# Driver.net
KiCad netlist of a schematic drawn in Altium Designer
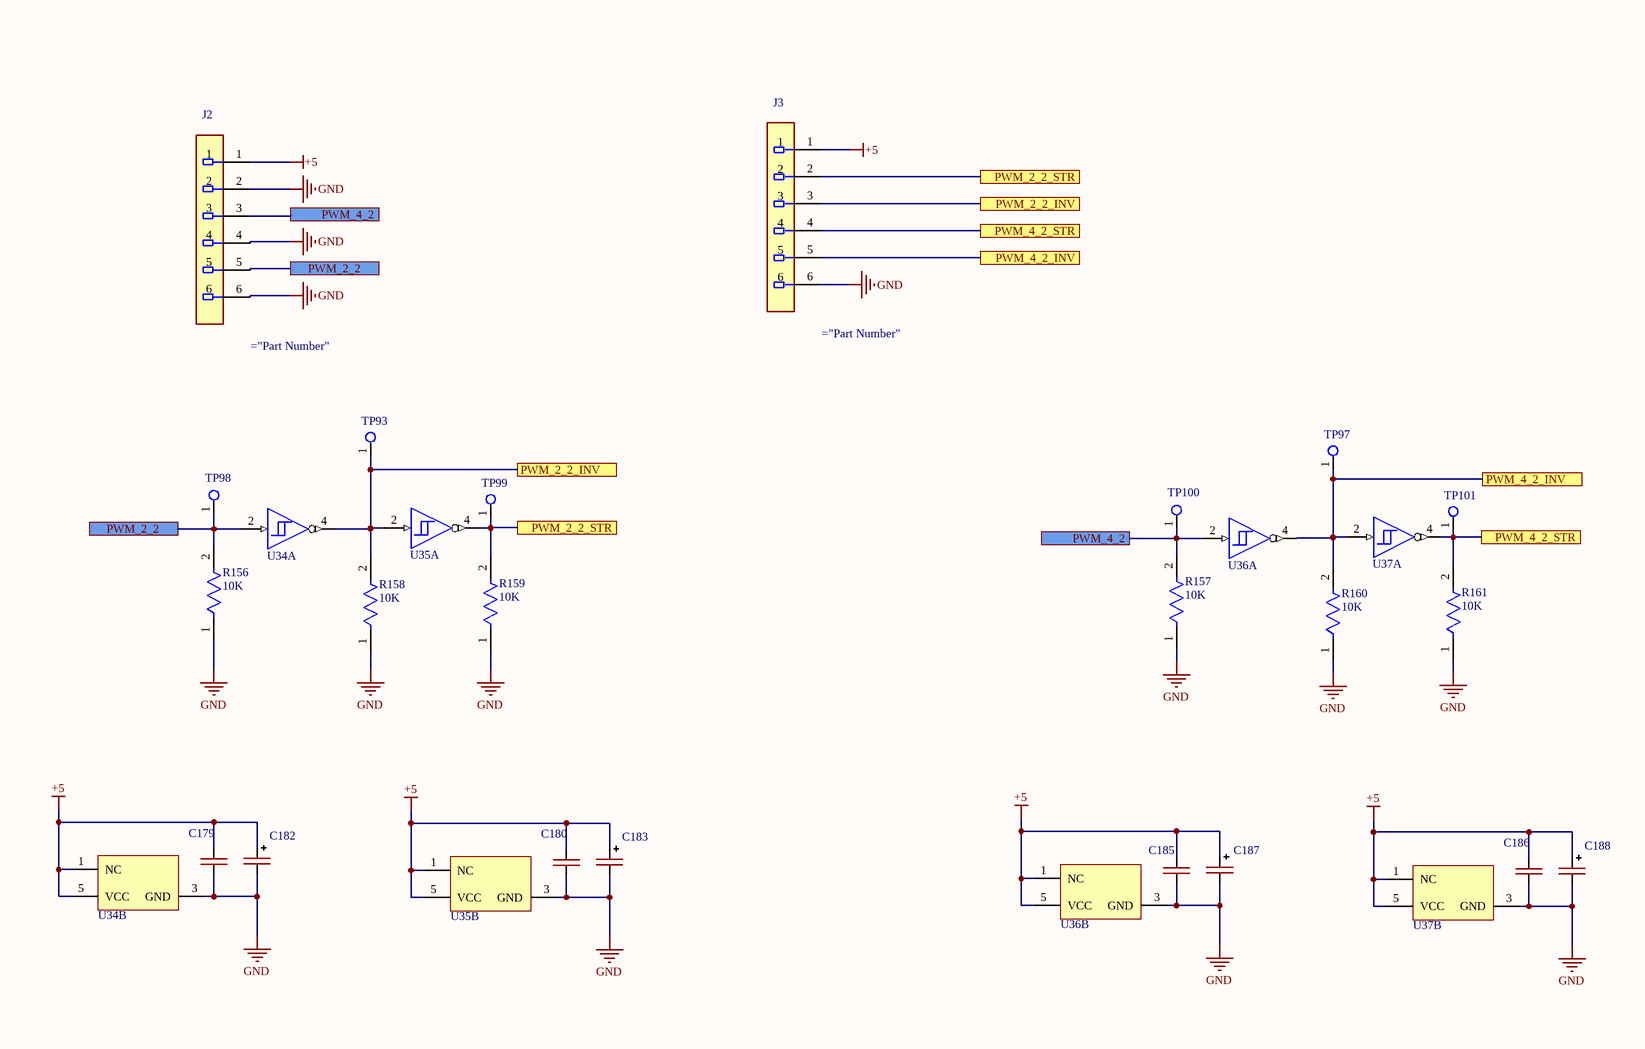
[diagram p0: Driver.SchDoc, left]
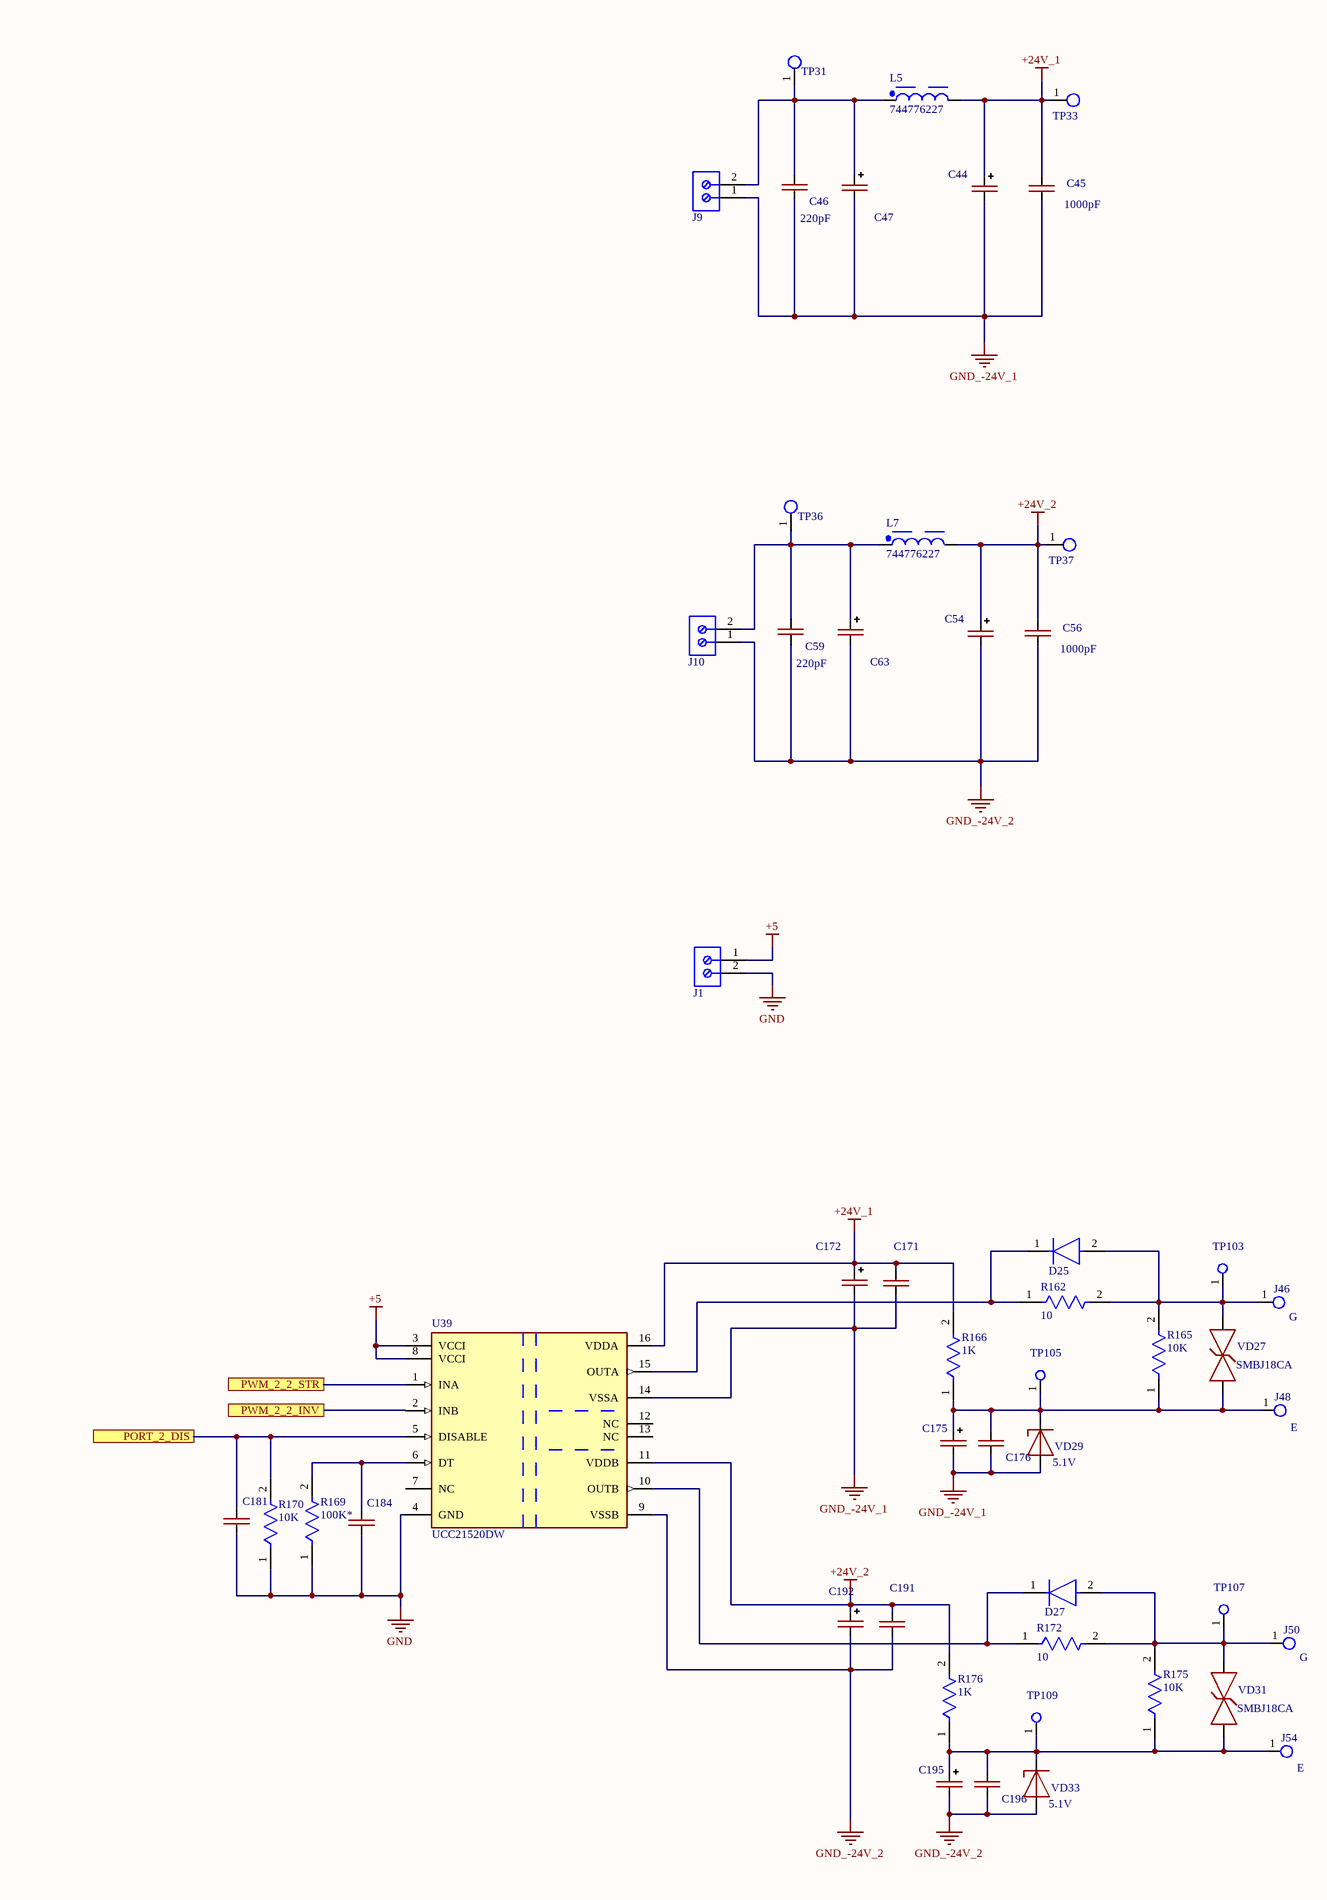
[diagram p1: Driver.SchDoc, middle]
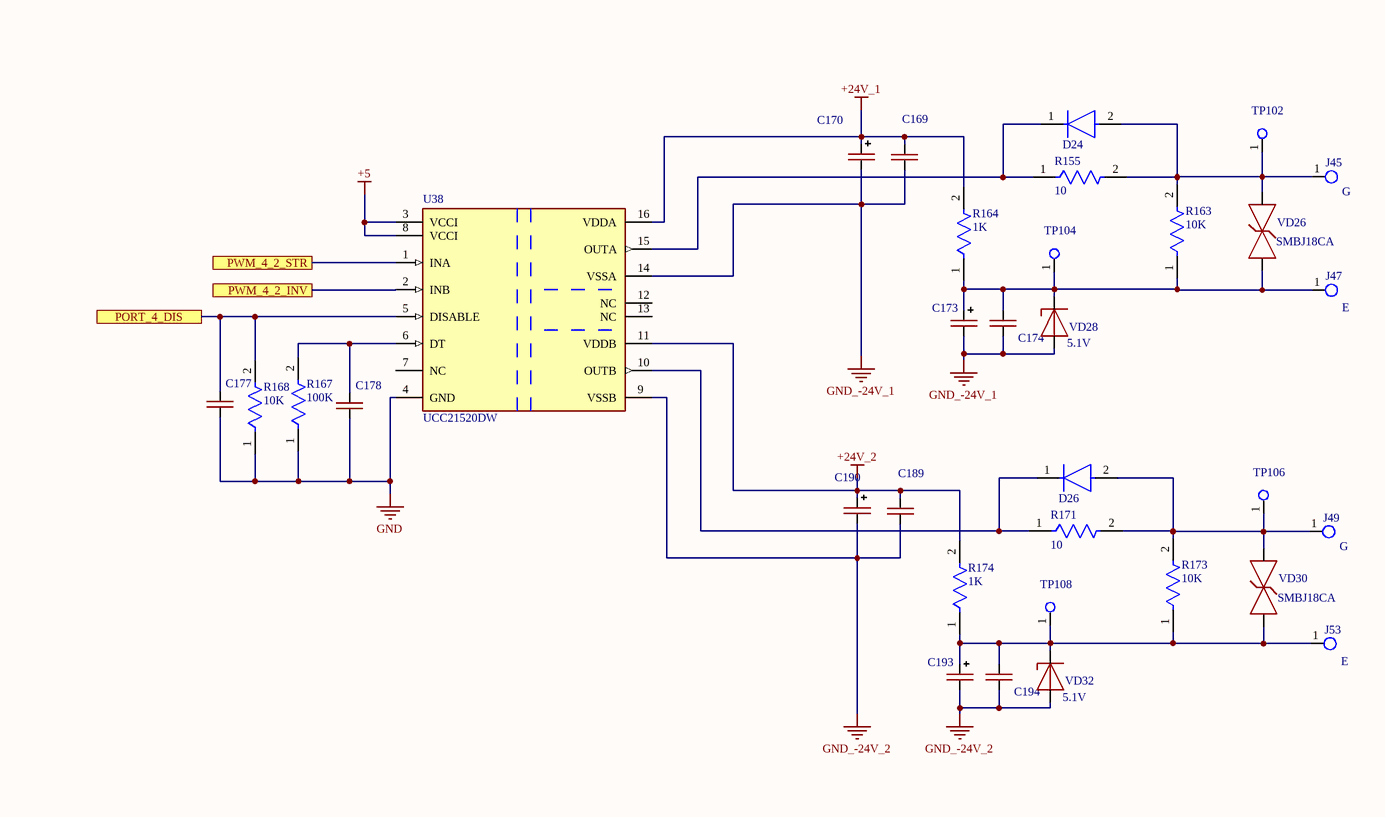
[diagram p2: Driver.SchDoc, right]

(export (version "E")
  (design (tool "Eeschema 10.0.6"))
  (components
    (comp (ref "C44")
      (value "~")
      (footprint "CAPPOL-12x25")
      (libsource (lib "PASSIVE_COMPONENTS") (part "CAP-POLAR"))
    )
    (comp (ref "C45")
      (value "1000pF")
      (footprint "CAP-1206")
      (libsource (lib "PASSIVE_COMPONENTS") (part "CAP-NON-POLAR"))
    )
    (comp (ref "C46")
      (value "220pF")
      (footprint "CAP-0805")
      (libsource (lib "PASSIVE_COMPONENTS") (part "CAP-NON-POLAR"))
    )
    (comp (ref "C47")
      (value "~")
      (footprint "CAPPOL-12x25")
      (libsource (lib "PASSIVE_COMPONENTS") (part "CAP-POLAR"))
    )
    (comp (ref "C54")
      (value "~")
      (footprint "CAPPOL-12x25")
      (libsource (lib "PASSIVE_COMPONENTS") (part "CAP-POLAR"))
    )
    (comp (ref "C56")
      (value "1000pF")
      (footprint "CAP-1206")
      (libsource (lib "PASSIVE_COMPONENTS") (part "CAP-NON-POLAR"))
    )
    (comp (ref "C59")
      (value "220pF")
      (footprint "CAP-0805")
      (libsource (lib "PASSIVE_COMPONENTS") (part "CAP-NON-POLAR"))
    )
    (comp (ref "C63")
      (value "~")
      (footprint "CAPPOL-12x25")
      (libsource (lib "PASSIVE_COMPONENTS") (part "CAP-POLAR"))
    )
    (comp (ref "C169")
      (value "CAP-NON-POLAR")
      (footprint "CAP-0805")
      (libsource (lib "PASSIVE_COMPONENTS") (part "CAP-NON-POLAR"))
    )
    (comp (ref "C170")
      (value "CAP-POLAR")
      (footprint "CAPPOL-16x25")
      (libsource (lib "PASSIVE_COMPONENTS") (part "CAP-POLAR"))
    )
    (comp (ref "C171")
      (value "CAP-NON-POLAR")
      (footprint "CAP-0805")
      (libsource (lib "PASSIVE_COMPONENTS") (part "CAP-NON-POLAR"))
    )
    (comp (ref "C172")
      (value "CAP-POLAR")
      (footprint "CAPPOL-16x25")
      (libsource (lib "PASSIVE_COMPONENTS") (part "CAP-POLAR"))
    )
    (comp (ref "C173")
      (value "CAP-POLAR")
      (footprint "CAP-TAN-D")
      (libsource (lib "PASSIVE_COMPONENTS") (part "CAP-POLAR"))
    )
    (comp (ref "C174")
      (value "CAP-NON-POLAR")
      (footprint "CAP-0805")
      (libsource (lib "PASSIVE_COMPONENTS") (part "CAP-NON-POLAR"))
    )
    (comp (ref "C175")
      (value "CAP-POLAR")
      (footprint "CAP-TAN-D")
      (libsource (lib "PASSIVE_COMPONENTS") (part "CAP-POLAR"))
    )
    (comp (ref "C176")
      (value "CAP-NON-POLAR")
      (footprint "CAP-0805")
      (libsource (lib "PASSIVE_COMPONENTS") (part "CAP-NON-POLAR"))
    )
    (comp (ref "C177")
      (value "CAP-NON-POLAR")
      (footprint "CAP-0805")
      (libsource (lib "PASSIVE_COMPONENTS") (part "CAP-NON-POLAR"))
    )
    (comp (ref "C178")
      (value "CAP-NON-POLAR")
      (footprint "CAP-0805")
      (libsource (lib "PASSIVE_COMPONENTS") (part "CAP-NON-POLAR"))
    )
    (comp (ref "C179")
      (value "CAP-NON-POLAR")
      (footprint "CAP-0805")
      (libsource (lib "PASSIVE_COMPONENTS") (part "CAP-NON-POLAR"))
    )
    (comp (ref "C180")
      (value "CAP-NON-POLAR")
      (footprint "CAP-0805")
      (libsource (lib "PASSIVE_COMPONENTS") (part "CAP-NON-POLAR"))
    )
    (comp (ref "C181")
      (value "CAP-NON-POLAR")
      (footprint "CAP-0805")
      (libsource (lib "PASSIVE_COMPONENTS") (part "CAP-NON-POLAR"))
    )
    (comp (ref "C182")
      (value "CAP-POLAR")
      (footprint "CAP-TAN-D")
      (libsource (lib "PASSIVE_COMPONENTS") (part "CAP-POLAR"))
    )
    (comp (ref "C183")
      (value "CAP-POLAR")
      (footprint "CAP-TAN-D")
      (libsource (lib "PASSIVE_COMPONENTS") (part "CAP-POLAR"))
    )
    (comp (ref "C184")
      (value "CAP-NON-POLAR")
      (footprint "CAP-0805")
      (libsource (lib "PASSIVE_COMPONENTS") (part "CAP-NON-POLAR"))
    )
    (comp (ref "C185")
      (value "CAP-NON-POLAR")
      (footprint "CAP-0805")
      (libsource (lib "PASSIVE_COMPONENTS") (part "CAP-NON-POLAR"))
    )
    (comp (ref "C186")
      (value "CAP-NON-POLAR")
      (footprint "CAP-0805")
      (libsource (lib "PASSIVE_COMPONENTS") (part "CAP-NON-POLAR"))
    )
    (comp (ref "C187")
      (value "CAP-POLAR")
      (footprint "CAP-TAN-D")
      (libsource (lib "PASSIVE_COMPONENTS") (part "CAP-POLAR"))
    )
    (comp (ref "C188")
      (value "CAP-POLAR")
      (footprint "CAP-TAN-D")
      (libsource (lib "PASSIVE_COMPONENTS") (part "CAP-POLAR"))
    )
    (comp (ref "C189")
      (value "CAP-NON-POLAR")
      (footprint "CAP-0805")
      (libsource (lib "PASSIVE_COMPONENTS") (part "CAP-NON-POLAR"))
    )
    (comp (ref "C190")
      (value "CAP-POLAR")
      (footprint "CAPPOL-16x25")
      (libsource (lib "PASSIVE_COMPONENTS") (part "CAP-POLAR"))
    )
    (comp (ref "C191")
      (value "CAP-NON-POLAR")
      (footprint "CAP-0805")
      (libsource (lib "PASSIVE_COMPONENTS") (part "CAP-NON-POLAR"))
    )
    (comp (ref "C192")
      (value "CAP-POLAR")
      (footprint "CAPPOL-16x25")
      (libsource (lib "PASSIVE_COMPONENTS") (part "CAP-POLAR"))
    )
    (comp (ref "C193")
      (value "CAP-POLAR")
      (footprint "CAP-TAN-D")
      (libsource (lib "PASSIVE_COMPONENTS") (part "CAP-POLAR"))
    )
    (comp (ref "C194")
      (value "CAP-NON-POLAR")
      (footprint "CAP-0805")
      (libsource (lib "PASSIVE_COMPONENTS") (part "CAP-NON-POLAR"))
    )
    (comp (ref "C195")
      (value "CAP-POLAR")
      (footprint "CAP-TAN-D")
      (libsource (lib "PASSIVE_COMPONENTS") (part "CAP-POLAR"))
    )
    (comp (ref "C196")
      (value "CAP-NON-POLAR")
      (footprint "CAP-0805")
      (libsource (lib "PASSIVE_COMPONENTS") (part "CAP-NON-POLAR"))
    )
    (comp (ref "D24") (value "US1G") (footprint "US1G_SMA") (libsource (lib "Diodes") (part "US1G")))
    (comp (ref "D25") (value "US1G") (footprint "US1G_SMA") (libsource (lib "Diodes") (part "US1G")))
    (comp (ref "D26") (value "US1G") (footprint "US1G_SMA") (libsource (lib "Diodes") (part "US1G")))
    (comp (ref "D27") (value "US1G") (footprint "US1G_SMA") (libsource (lib "Diodes") (part "US1G")))
    (comp (ref "J1")
      (value "691101710002")
      (footprint "691101710002")
      (description "WR-TBL Series 101 Horizontal Entry Modular, THT, pitch 5mm, 2p")
      (fields (field (name "MANUFACTURER") "Wurth Elektronik"))
      (libsource (lib "") (part "691101710002_2"))
    )
    (comp (ref "J2")
      (value "~")
      (footprint "Sullins_SWR25X-NRTC-S06-ST-BA_MFG")
      (libsource (lib "Connectors") (part "SWR25X-NRTC-S06-ST-BA"))
    )
    (comp (ref "J3")
      (value "~")
      (footprint "Sullins_SWR25X-NRTC-S06-ST-BA_MFG")
      (libsource (lib "Connectors") (part "SWR25X-NRTC-S06-ST-BA"))
    )
    (comp (ref "J9")
      (value "691101710002")
      (footprint "691101710002")
      (description "WR-TBL Series 101 Horizontal Entry Modular, THT, pitch 5mm, 2p")
      (fields (field (name "MANUFACTURER") "Wurth Elektronik"))
      (libsource (lib "") (part "691101710002_1"))
    )
    (comp (ref "J10")
      (value "691101710002")
      (footprint "691101710002")
      (description "WR-TBL Series 101 Horizontal Entry Modular, THT, pitch 5mm, 2p")
      (fields (field (name "MANUFACTURER") "Wurth Elektronik"))
      (libsource (lib "Altium_WR-TBL (rev22b)") (part "691101710002"))
    )
    (comp (ref "J45")
      (value "G")
      (footprint "Klema_PCB_15A")
      (libsource (lib "Connectors") (part "Klema_15_A"))
    )
    (comp (ref "J46")
      (value "G")
      (footprint "Klema_PCB_15A")
      (libsource (lib "Connectors") (part "Klema_15_A"))
    )
    (comp (ref "J47")
      (value "E")
      (footprint "Klema_PCB_15A")
      (libsource (lib "Connectors") (part "Klema_15_A"))
    )
    (comp (ref "J48")
      (value "E")
      (footprint "Klema_PCB_15A")
      (libsource (lib "Connectors") (part "Klema_15_A"))
    )
    (comp (ref "J49")
      (value "G")
      (footprint "Klema_PCB_15A")
      (libsource (lib "Connectors") (part "Klema_15_A"))
    )
    (comp (ref "J50")
      (value "G")
      (footprint "Klema_PCB_15A")
      (libsource (lib "Connectors") (part "Klema_15_A"))
    )
    (comp (ref "J53")
      (value "E")
      (footprint "Klema_PCB_15A")
      (libsource (lib "Connectors") (part "Klema_15_A"))
    )
    (comp (ref "J54")
      (value "E")
      (footprint "Klema_PCB_15A")
      (libsource (lib "Connectors") (part "Klema_15_A"))
    )
    (comp (ref "L5")
      (value "744776227")
      (footprint "WE-PD2_1054")
      (libsource (lib "Altium Content Vault") (part "Inductor - 2"))
    )
    (comp (ref "L7")
      (value "744776227")
      (footprint "WE-PD2_1054")
      (libsource (lib "Altium Content Vault") (part "Inductor - 2"))
    )
    (comp (ref "R155")
      (value "10")
      (footprint "RES-2512")
      (libsource (lib "PASSIVE_COMPONENTS") (part "RES-CONST"))
    )
    (comp (ref "R156")
      (value "10K")
      (footprint "RES-0805")
      (libsource (lib "PASSIVE_COMPONENTS") (part "RES-CONST"))
    )
    (comp (ref "R157")
      (value "10K")
      (footprint "RES-0805")
      (libsource (lib "PASSIVE_COMPONENTS") (part "RES-CONST"))
    )
    (comp (ref "R158")
      (value "10K")
      (footprint "RES-0805")
      (libsource (lib "PASSIVE_COMPONENTS") (part "RES-CONST"))
    )
    (comp (ref "R159")
      (value "10K")
      (footprint "RES-0805")
      (libsource (lib "PASSIVE_COMPONENTS") (part "RES-CONST"))
    )
    (comp (ref "R160")
      (value "10K")
      (footprint "RES-0805")
      (libsource (lib "PASSIVE_COMPONENTS") (part "RES-CONST"))
    )
    (comp (ref "R161")
      (value "10K")
      (footprint "RES-0805")
      (libsource (lib "PASSIVE_COMPONENTS") (part "RES-CONST"))
    )
    (comp (ref "R162")
      (value "10")
      (footprint "RES-2512")
      (libsource (lib "PASSIVE_COMPONENTS") (part "RES-CONST"))
    )
    (comp (ref "R163")
      (value "10K")
      (footprint "RES-0805")
      (libsource (lib "PASSIVE_COMPONENTS") (part "RES-CONST"))
    )
    (comp (ref "R164")
      (value "1K")
      (footprint "RES-2512")
      (libsource (lib "PASSIVE_COMPONENTS") (part "RES-CONST"))
    )
    (comp (ref "R165")
      (value "10K")
      (footprint "RES-0805")
      (libsource (lib "PASSIVE_COMPONENTS") (part "RES-CONST"))
    )
    (comp (ref "R166")
      (value "1K")
      (footprint "RES-2512")
      (libsource (lib "PASSIVE_COMPONENTS") (part "RES-CONST"))
    )
    (comp (ref "R167")
      (value "100K")
      (footprint "RES-0805")
      (libsource (lib "PASSIVE_COMPONENTS") (part "RES-CONST"))
    )
    (comp (ref "R168")
      (value "10K")
      (footprint "RES-0805")
      (libsource (lib "PASSIVE_COMPONENTS") (part "RES-CONST"))
    )
    (comp (ref "R169")
      (value "100K*")
      (footprint "RES-0805")
      (description "100K")
      (libsource (lib "PASSIVE_COMPONENTS") (part "RES-CONST"))
    )
    (comp (ref "R170")
      (value "10K")
      (footprint "RES-0805")
      (libsource (lib "PASSIVE_COMPONENTS") (part "RES-CONST"))
    )
    (comp (ref "R171")
      (value "10")
      (footprint "RES-2512")
      (libsource (lib "PASSIVE_COMPONENTS") (part "RES-CONST"))
    )
    (comp (ref "R172")
      (value "10")
      (footprint "RES-2512")
      (libsource (lib "PASSIVE_COMPONENTS") (part "RES-CONST"))
    )
    (comp (ref "R173")
      (value "10K")
      (footprint "RES-0805")
      (libsource (lib "PASSIVE_COMPONENTS") (part "RES-CONST"))
    )
    (comp (ref "R174")
      (value "1K")
      (footprint "RES-2512")
      (libsource (lib "PASSIVE_COMPONENTS") (part "RES-CONST"))
    )
    (comp (ref "R175")
      (value "10K")
      (footprint "RES-0805")
      (libsource (lib "PASSIVE_COMPONENTS") (part "RES-CONST"))
    )
    (comp (ref "R176")
      (value "1K")
      (footprint "RES-2512")
      (libsource (lib "PASSIVE_COMPONENTS") (part "RES-CONST"))
    )
    (comp (ref "TP31")
      (value "Test_Point_PCB")
      (footprint "Test_Point")
      (description "Test_Point")
      (libsource (lib "Test_Point") (part "TP_PCB?"))
    )
    (comp (ref "TP33")
      (value "Test_Point_PCB")
      (footprint "Test_Point")
      (description "Test_Point")
      (libsource (lib "Test_Point") (part "TP_PCB?"))
    )
    (comp (ref "TP36")
      (value "Test_Point_PCB")
      (footprint "Test_Point")
      (description "Test_Point")
      (libsource (lib "Test_Point") (part "TP_PCB?"))
    )
    (comp (ref "TP37")
      (value "Test_Point_PCB")
      (footprint "Test_Point")
      (description "Test_Point")
      (libsource (lib "Test_Point") (part "TP_PCB?"))
    )
    (comp (ref "TP93")
      (value "Test_Point_PCB")
      (footprint "Test_Point")
      (description "Test_Point")
      (libsource (lib "Connectors") (part "TP_PCB?"))
    )
    (comp (ref "TP97")
      (value "Test_Point_PCB")
      (footprint "Test_Point")
      (description "Test_Point")
      (libsource (lib "Connectors") (part "TP_PCB?"))
    )
    (comp (ref "TP98")
      (value "Test_Point_PCB")
      (footprint "Test_Point")
      (description "Test_Point")
      (libsource (lib "Connectors") (part "TP_PCB?"))
    )
    (comp (ref "TP99")
      (value "Test_Point_PCB")
      (footprint "Test_Point")
      (description "Test_Point")
      (libsource (lib "Connectors") (part "TP_PCB?"))
    )
    (comp (ref "TP100")
      (value "Test_Point_PCB")
      (footprint "Test_Point")
      (description "Test_Point")
      (libsource (lib "Connectors") (part "TP_PCB?"))
    )
    (comp (ref "TP101")
      (value "Test_Point_PCB")
      (footprint "Test_Point")
      (description "Test_Point")
      (libsource (lib "Connectors") (part "TP_PCB?"))
    )
    (comp (ref "TP102")
      (value "Test_Point_PCB")
      (footprint "Test_Point")
      (description "Test_Point")
      (libsource (lib "Connectors") (part "TP_PCB?"))
    )
    (comp (ref "TP103")
      (value "Test_Point_PCB")
      (footprint "Test_Point")
      (description "Test_Point")
      (libsource (lib "Connectors") (part "TP_PCB?"))
    )
    (comp (ref "TP104")
      (value "Test_Point_PCB")
      (footprint "Test_Point")
      (description "Test_Point")
      (libsource (lib "Connectors") (part "TP_PCB?"))
    )
    (comp (ref "TP105")
      (value "Test_Point_PCB")
      (footprint "Test_Point")
      (description "Test_Point")
      (libsource (lib "Connectors") (part "TP_PCB?"))
    )
    (comp (ref "TP106")
      (value "Test_Point_PCB")
      (footprint "Test_Point")
      (description "Test_Point")
      (libsource (lib "Connectors") (part "TP_PCB?"))
    )
    (comp (ref "TP107")
      (value "Test_Point_PCB")
      (footprint "Test_Point")
      (description "Test_Point")
      (libsource (lib "Connectors") (part "TP_PCB?"))
    )
    (comp (ref "TP108")
      (value "Test_Point_PCB")
      (footprint "Test_Point")
      (description "Test_Point")
      (libsource (lib "Connectors") (part "TP_PCB?"))
    )
    (comp (ref "TP109")
      (value "Test_Point_PCB")
      (footprint "Test_Point")
      (description "Test_Point")
      (libsource (lib "Connectors") (part "TP_PCB?"))
    )
    (comp (ref "U34")
      (value "74LVC1G14")
      (footprint "SOT23-5_N")
      (libsource (lib "Integrated_Circuts") (part "74LVC1G14"))
    )
    (comp (ref "U35")
      (value "74LVC1G14")
      (footprint "SOT23-5_N")
      (libsource (lib "Integrated_Circuts") (part "74LVC1G14"))
    )
    (comp (ref "U36")
      (value "74LVC1G14")
      (footprint "SOT23-5_N")
      (libsource (lib "Integrated_Circuts") (part "74LVC1G14"))
    )
    (comp (ref "U37")
      (value "74LVC1G14")
      (footprint "SOT23-5_N")
      (libsource (lib "Integrated_Circuts") (part "74LVC1G14"))
    )
    (comp (ref "U38")
      (value "UCC21520DW")
      (footprint "FP-DW0016B-MFG")
      (libsource (lib "Integrated_Circuts") (part "UCC21520DW"))
    )
    (comp (ref "U39")
      (value "UCC21520DW")
      (footprint "FP-DW0016B-MFG")
      (libsource (lib "Integrated_Circuts") (part "UCC21520DW"))
    )
    (comp (ref "VD26")
      (value "SMBJ18CA")
      (footprint "DO-214AA")
      (libsource (lib "Diodes") (part "Suppressor"))
    )
    (comp (ref "VD27")
      (value "SMBJ18CA")
      (footprint "DO-214AA")
      (libsource (lib "Diodes") (part "Suppressor"))
    )
    (comp (ref "VD28") (value "5.1V") (footprint "DO-35") (libsource (lib "Diodes") (part "ZENER")))
    (comp (ref "VD29") (value "5.1V") (footprint "DO-35") (libsource (lib "Diodes") (part "ZENER")))
    (comp (ref "VD30")
      (value "SMBJ18CA")
      (footprint "DO-214AA")
      (libsource (lib "Diodes") (part "Suppressor"))
    )
    (comp (ref "VD31")
      (value "SMBJ18CA")
      (footprint "DO-214AA")
      (libsource (lib "Diodes") (part "Suppressor"))
    )
    (comp (ref "VD32") (value "5.1V") (footprint "DO-35") (libsource (lib "Diodes") (part "ZENER")))
    (comp (ref "VD33") (value "5.1V") (footprint "DO-35") (libsource (lib "Diodes") (part "ZENER")))
  )
  (nets
    (net (code "1") (name "+5") (class "Default")
      (node (ref "C179") (pin "2") (pinfunction "2_2") (pintype "passive"))
      (node (ref "C180") (pin "2") (pinfunction "2_2") (pintype "passive"))
      (node (ref "C182") (pin "1") (pinfunction "+_1") (pintype "passive"))
      (node (ref "C183") (pin "1") (pinfunction "+_1") (pintype "passive"))
      (node (ref "C185") (pin "2") (pinfunction "2_2") (pintype "passive"))
      (node (ref "C186") (pin "2") (pinfunction "2_2") (pintype "passive"))
      (node (ref "C187") (pin "1") (pinfunction "+_1") (pintype "passive"))
      (node (ref "C188") (pin "1") (pinfunction "+_1") (pintype "passive"))
      (node (ref "J1") (pin "1") (pinfunction "1_1") (pintype "passive"))
      (node (ref "J2") (pin "1") (pinfunction "1_1") (pintype "passive"))
      (node (ref "J3") (pin "1") (pinfunction "1_1") (pintype "passive"))
      (node (ref "U34") (pin "1") (pinfunction "NC_1") (pintype "passive"))
      (node (ref "U34") (pin "5") (pinfunction "VCC_5") (pintype "power_in"))
      (node (ref "U35") (pin "1") (pinfunction "NC_1") (pintype "passive"))
      (node (ref "U35") (pin "5") (pinfunction "VCC_5") (pintype "power_in"))
      (node (ref "U36") (pin "1") (pinfunction "NC_1") (pintype "passive"))
      (node (ref "U36") (pin "5") (pinfunction "VCC_5") (pintype "power_in"))
      (node (ref "U37") (pin "1") (pinfunction "NC_1") (pintype "passive"))
      (node (ref "U37") (pin "5") (pinfunction "VCC_5") (pintype "power_in"))
      (node (ref "U38") (pin "3") (pinfunction "VCCI_3") (pintype "power_in"))
      (node (ref "U38") (pin "8") (pinfunction "VCCI_8") (pintype "power_in"))
      (node (ref "U39") (pin "3") (pinfunction "VCCI_3") (pintype "power_in"))
      (node (ref "U39") (pin "8") (pinfunction "VCCI_8") (pintype "power_in"))
    )
    (net (code "2") (name "+24V_1") (class "Default")
      (node (ref "C169") (pin "2") (pinfunction "2_2") (pintype "passive"))
      (node (ref "C170") (pin "1") (pinfunction "+_1") (pintype "passive"))
      (node (ref "C171") (pin "2") (pinfunction "2_2") (pintype "passive"))
      (node (ref "C172") (pin "1") (pinfunction "+_1") (pintype "passive"))
      (node (ref "C44") (pin "1") (pinfunction "+_1") (pintype "passive"))
      (node (ref "C45") (pin "2") (pinfunction "2_2") (pintype "passive"))
      (node (ref "L5") (pin "2") (pinfunction "2_2") (pintype "passive"))
      (node (ref "R164") (pin "2") (pinfunction "2_2") (pintype "passive"))
      (node (ref "R166") (pin "2") (pinfunction "2_2") (pintype "passive"))
      (node (ref "TP33") (pin "1") (pinfunction "G9_1") (pintype "passive"))
      (node (ref "U38") (pin "16") (pinfunction "VDDA_16") (pintype "power_in"))
      (node (ref "U39") (pin "16") (pinfunction "VDDA_16") (pintype "power_in"))
    )
    (net (code "3") (name "+24V_2") (class "Default")
      (node (ref "C189") (pin "2") (pinfunction "2_2") (pintype "passive"))
      (node (ref "C190") (pin "1") (pinfunction "+_1") (pintype "passive"))
      (node (ref "C191") (pin "2") (pinfunction "2_2") (pintype "passive"))
      (node (ref "C192") (pin "1") (pinfunction "+_1") (pintype "passive"))
      (node (ref "C54") (pin "1") (pinfunction "+_1") (pintype "passive"))
      (node (ref "C56") (pin "2") (pinfunction "2_2") (pintype "passive"))
      (node (ref "L7") (pin "2") (pinfunction "2_2") (pintype "passive"))
      (node (ref "R174") (pin "2") (pinfunction "2_2") (pintype "passive"))
      (node (ref "R176") (pin "2") (pinfunction "2_2") (pintype "passive"))
      (node (ref "TP37") (pin "1") (pinfunction "G9_1") (pintype "passive"))
      (node (ref "U38") (pin "11") (pinfunction "VDDB_11") (pintype "power_in"))
      (node (ref "U39") (pin "11") (pinfunction "VDDB_11") (pintype "power_in"))
    )
    (net (code "4") (name "/PORT_2_DIS") (class "Default")
      (node (ref "C181") (pin "2") (pinfunction "2_2") (pintype "passive"))
      (node (ref "R170") (pin "2") (pinfunction "2_2") (pintype "passive"))
      (node (ref "U39") (pin "5") (pinfunction "DISABLE_5") (pintype "input"))
    )
    (net (code "5") (name "/PORT_4_DIS") (class "Default")
      (node (ref "C177") (pin "2") (pinfunction "2_2") (pintype "passive"))
      (node (ref "R168") (pin "2") (pinfunction "2_2") (pintype "passive"))
      (node (ref "U38") (pin "5") (pinfunction "DISABLE_5") (pintype "input"))
    )
    (net (code "6") (name "/PWM_2_2") (class "Default")
      (node (ref "J2") (pin "5") (pinfunction "5_5") (pintype "passive"))
      (node (ref "R156") (pin "2") (pinfunction "2_2") (pintype "passive"))
      (node (ref "TP98") (pin "1") (pinfunction "G9_1") (pintype "passive"))
      (node (ref "U34") (pin "2") (pinfunction "A_2") (pintype "input"))
    )
    (net (code "7") (name "/PWM_2_2_INV") (class "Default")
      (node (ref "J3") (pin "3") (pinfunction "3_3") (pintype "passive"))
      (node (ref "R158") (pin "2") (pinfunction "2_2") (pintype "passive"))
      (node (ref "TP93") (pin "1") (pinfunction "G9_1") (pintype "passive"))
      (node (ref "U34") (pin "4") (pinfunction "Y_4") (pintype "output"))
      (node (ref "U35") (pin "2") (pinfunction "A_2") (pintype "input"))
      (node (ref "U39") (pin "2") (pinfunction "INB_2") (pintype "input"))
    )
    (net (code "8") (name "/PWM_2_2_STR") (class "Default")
      (node (ref "J3") (pin "2") (pinfunction "2_2") (pintype "passive"))
      (node (ref "R159") (pin "2") (pinfunction "2_2") (pintype "passive"))
      (node (ref "TP99") (pin "1") (pinfunction "G9_1") (pintype "passive"))
      (node (ref "U35") (pin "4") (pinfunction "Y_4") (pintype "output"))
      (node (ref "U39") (pin "1") (pinfunction "INA_1") (pintype "input"))
    )
    (net (code "9") (name "/PWM_4_2") (class "Default")
      (node (ref "J2") (pin "3") (pinfunction "3_3") (pintype "passive"))
      (node (ref "R157") (pin "2") (pinfunction "2_2") (pintype "passive"))
      (node (ref "TP100") (pin "1") (pinfunction "G9_1") (pintype "passive"))
      (node (ref "U36") (pin "2") (pinfunction "A_2") (pintype "input"))
    )
    (net (code "10") (name "/PWM_4_2_INV") (class "Default")
      (node (ref "J3") (pin "5") (pinfunction "5_5") (pintype "passive"))
      (node (ref "R160") (pin "2") (pinfunction "2_2") (pintype "passive"))
      (node (ref "TP97") (pin "1") (pinfunction "G9_1") (pintype "passive"))
      (node (ref "U36") (pin "4") (pinfunction "Y_4") (pintype "output"))
      (node (ref "U37") (pin "2") (pinfunction "A_2") (pintype "input"))
      (node (ref "U38") (pin "2") (pinfunction "INB_2") (pintype "input"))
    )
    (net (code "11") (name "/PWM_4_2_STR") (class "Default")
      (node (ref "J3") (pin "4") (pinfunction "4_4") (pintype "passive"))
      (node (ref "R161") (pin "2") (pinfunction "2_2") (pintype "passive"))
      (node (ref "TP101") (pin "1") (pinfunction "G9_1") (pintype "passive"))
      (node (ref "U37") (pin "4") (pinfunction "Y_4") (pintype "output"))
      (node (ref "U38") (pin "1") (pinfunction "INA_1") (pintype "input"))
    )
    (net (code "12") (name "GND") (class "Default")
      (node (ref "C177") (pin "1") (pinfunction "1_1") (pintype "passive"))
      (node (ref "C178") (pin "1") (pinfunction "1_1") (pintype "passive"))
      (node (ref "C179") (pin "1") (pinfunction "1_1") (pintype "passive"))
      (node (ref "C180") (pin "1") (pinfunction "1_1") (pintype "passive"))
      (node (ref "C181") (pin "1") (pinfunction "1_1") (pintype "passive"))
      (node (ref "C182") (pin "2") (pinfunction "-_2") (pintype "passive"))
      (node (ref "C183") (pin "2") (pinfunction "-_2") (pintype "passive"))
      (node (ref "C184") (pin "1") (pinfunction "1_1") (pintype "passive"))
      (node (ref "C185") (pin "1") (pinfunction "1_1") (pintype "passive"))
      (node (ref "C186") (pin "1") (pinfunction "1_1") (pintype "passive"))
      (node (ref "C187") (pin "2") (pinfunction "-_2") (pintype "passive"))
      (node (ref "C188") (pin "2") (pinfunction "-_2") (pintype "passive"))
      (node (ref "J1") (pin "2") (pinfunction "2_2") (pintype "passive"))
      (node (ref "J2") (pin "2") (pinfunction "2_2") (pintype "passive"))
      (node (ref "J2") (pin "4") (pinfunction "4_4") (pintype "passive"))
      (node (ref "J2") (pin "6") (pinfunction "6_6") (pintype "passive"))
      (node (ref "J3") (pin "6") (pinfunction "6_6") (pintype "passive"))
      (node (ref "R156") (pin "1") (pinfunction "1_1") (pintype "passive"))
      (node (ref "R157") (pin "1") (pinfunction "1_1") (pintype "passive"))
      (node (ref "R158") (pin "1") (pinfunction "1_1") (pintype "passive"))
      (node (ref "R159") (pin "1") (pinfunction "1_1") (pintype "passive"))
      (node (ref "R160") (pin "1") (pinfunction "1_1") (pintype "passive"))
      (node (ref "R161") (pin "1") (pinfunction "1_1") (pintype "passive"))
      (node (ref "R167") (pin "1") (pinfunction "1_1") (pintype "passive"))
      (node (ref "R168") (pin "1") (pinfunction "1_1") (pintype "passive"))
      (node (ref "R169") (pin "1") (pinfunction "1_1") (pintype "passive"))
      (node (ref "R170") (pin "1") (pinfunction "1_1") (pintype "passive"))
      (node (ref "U34") (pin "3") (pinfunction "GND_3") (pintype "power_in"))
      (node (ref "U35") (pin "3") (pinfunction "GND_3") (pintype "power_in"))
      (node (ref "U36") (pin "3") (pinfunction "GND_3") (pintype "power_in"))
      (node (ref "U37") (pin "3") (pinfunction "GND_3") (pintype "power_in"))
      (node (ref "U38") (pin "4") (pinfunction "GND_4") (pintype "power_in"))
      (node (ref "U39") (pin "4") (pinfunction "GND_4") (pintype "power_in"))
    )
    (net (code "13") (name "GND_-24V_1") (class "Default")
      (node (ref "C169") (pin "1") (pinfunction "1_1") (pintype "passive"))
      (node (ref "C170") (pin "2") (pinfunction "-_2") (pintype "passive"))
      (node (ref "C171") (pin "1") (pinfunction "1_1") (pintype "passive"))
      (node (ref "C172") (pin "2") (pinfunction "-_2") (pintype "passive"))
      (node (ref "C173") (pin "2") (pinfunction "-_2") (pintype "passive"))
      (node (ref "C174") (pin "1") (pinfunction "1_1") (pintype "passive"))
      (node (ref "C175") (pin "2") (pinfunction "-_2") (pintype "passive"))
      (node (ref "C176") (pin "1") (pinfunction "1_1") (pintype "passive"))
      (node (ref "C44") (pin "2") (pinfunction "-_2") (pintype "passive"))
      (node (ref "C45") (pin "1") (pinfunction "1_1") (pintype "passive"))
      (node (ref "C46") (pin "1") (pinfunction "1_1") (pintype "passive"))
      (node (ref "C47") (pin "2") (pinfunction "-_2") (pintype "passive"))
      (node (ref "J9") (pin "1") (pinfunction "1_1") (pintype "passive"))
      (node (ref "U38") (pin "14") (pinfunction "VSSA_14") (pintype "power_in"))
      (node (ref "U39") (pin "14") (pinfunction "VSSA_14") (pintype "power_in"))
      (node (ref "VD28") (pin "2") (pinfunction "A_2") (pintype "passive"))
      (node (ref "VD29") (pin "2") (pinfunction "A_2") (pintype "passive"))
    )
    (net (code "14") (name "GND_-24V_2") (class "Default")
      (node (ref "C189") (pin "1") (pinfunction "1_1") (pintype "passive"))
      (node (ref "C190") (pin "2") (pinfunction "-_2") (pintype "passive"))
      (node (ref "C191") (pin "1") (pinfunction "1_1") (pintype "passive"))
      (node (ref "C192") (pin "2") (pinfunction "-_2") (pintype "passive"))
      (node (ref "C193") (pin "2") (pinfunction "-_2") (pintype "passive"))
      (node (ref "C194") (pin "1") (pinfunction "1_1") (pintype "passive"))
      (node (ref "C195") (pin "2") (pinfunction "-_2") (pintype "passive"))
      (node (ref "C196") (pin "1") (pinfunction "1_1") (pintype "passive"))
      (node (ref "C54") (pin "2") (pinfunction "-_2") (pintype "passive"))
      (node (ref "C56") (pin "1") (pinfunction "1_1") (pintype "passive"))
      (node (ref "C59") (pin "1") (pinfunction "1_1") (pintype "passive"))
      (node (ref "C63") (pin "2") (pinfunction "-_2") (pintype "passive"))
      (node (ref "J10") (pin "1") (pinfunction "1_1") (pintype "passive"))
      (node (ref "U38") (pin "9") (pinfunction "VSSB_9") (pintype "power_in"))
      (node (ref "U39") (pin "9") (pinfunction "VSSB_9") (pintype "power_in"))
      (node (ref "VD32") (pin "2") (pinfunction "A_2") (pintype "passive"))
      (node (ref "VD33") (pin "2") (pinfunction "A_2") (pintype "passive"))
    )
    (net (code "15") (name "Net-(C47-+)") (class "Default")
      (node (ref "C46") (pin "2") (pinfunction "2_2") (pintype "passive"))
      (node (ref "C47") (pin "1") (pinfunction "+_1") (pintype "passive"))
      (node (ref "J9") (pin "2") (pinfunction "2_2") (pintype "passive"))
      (node (ref "L5") (pin "1") (pinfunction "1_1") (pintype "passive"))
      (node (ref "TP31") (pin "1") (pinfunction "G9_1") (pintype "passive"))
    )
    (net (code "16") (name "Net-(C63-+)") (class "Default")
      (node (ref "C59") (pin "2") (pinfunction "2_2") (pintype "passive"))
      (node (ref "C63") (pin "1") (pinfunction "+_1") (pintype "passive"))
      (node (ref "J10") (pin "2") (pinfunction "2_2") (pintype "passive"))
      (node (ref "L7") (pin "1") (pinfunction "1_1") (pintype "passive"))
      (node (ref "TP36") (pin "1") (pinfunction "G9_1") (pintype "passive"))
    )
    (net (code "17") (name "Net-(C173-+)") (class "Default")
      (node (ref "C173") (pin "1") (pinfunction "+_1") (pintype "passive"))
      (node (ref "C174") (pin "2") (pinfunction "2_2") (pintype "passive"))
      (node (ref "J47") (pin "1") (pinfunction "0_1") (pintype "passive"))
      (node (ref "R163") (pin "1") (pinfunction "1_1") (pintype "passive"))
      (node (ref "R164") (pin "1") (pinfunction "1_1") (pintype "passive"))
      (node (ref "TP104") (pin "1") (pinfunction "G9_1") (pintype "passive"))
      (node (ref "VD26") (pin "1") (pinfunction "C_1") (pintype "passive"))
      (node (ref "VD28") (pin "1") (pinfunction "C_1") (pintype "passive"))
    )
    (net (code "18") (name "Net-(C175-+)") (class "Default")
      (node (ref "C175") (pin "1") (pinfunction "+_1") (pintype "passive"))
      (node (ref "C176") (pin "2") (pinfunction "2_2") (pintype "passive"))
      (node (ref "J48") (pin "1") (pinfunction "0_1") (pintype "passive"))
      (node (ref "R165") (pin "1") (pinfunction "1_1") (pintype "passive"))
      (node (ref "R166") (pin "1") (pinfunction "1_1") (pintype "passive"))
      (node (ref "TP105") (pin "1") (pinfunction "G9_1") (pintype "passive"))
      (node (ref "VD27") (pin "1") (pinfunction "C_1") (pintype "passive"))
      (node (ref "VD29") (pin "1") (pinfunction "C_1") (pintype "passive"))
    )
    (net (code "19") (name "Net-(C193-+)") (class "Default")
      (node (ref "C193") (pin "1") (pinfunction "+_1") (pintype "passive"))
      (node (ref "C194") (pin "2") (pinfunction "2_2") (pintype "passive"))
      (node (ref "J53") (pin "1") (pinfunction "0_1") (pintype "passive"))
      (node (ref "R173") (pin "1") (pinfunction "1_1") (pintype "passive"))
      (node (ref "R174") (pin "1") (pinfunction "1_1") (pintype "passive"))
      (node (ref "TP108") (pin "1") (pinfunction "G9_1") (pintype "passive"))
      (node (ref "VD30") (pin "1") (pinfunction "C_1") (pintype "passive"))
      (node (ref "VD32") (pin "1") (pinfunction "C_1") (pintype "passive"))
    )
    (net (code "20") (name "Net-(C195-+)") (class "Default")
      (node (ref "C195") (pin "1") (pinfunction "+_1") (pintype "passive"))
      (node (ref "C196") (pin "2") (pinfunction "2_2") (pintype "passive"))
      (node (ref "J54") (pin "1") (pinfunction "0_1") (pintype "passive"))
      (node (ref "R175") (pin "1") (pinfunction "1_1") (pintype "passive"))
      (node (ref "R176") (pin "1") (pinfunction "1_1") (pintype "passive"))
      (node (ref "TP109") (pin "1") (pinfunction "G9_1") (pintype "passive"))
      (node (ref "VD31") (pin "1") (pinfunction "C_1") (pintype "passive"))
      (node (ref "VD33") (pin "1") (pinfunction "C_1") (pintype "passive"))
    )
    (net (code "21") (name "Net-(D24-A)") (class "Default")
      (node (ref "D24") (pin "2") (pinfunction "A_2") (pintype "passive"))
      (node (ref "J45") (pin "1") (pinfunction "0_1") (pintype "passive"))
      (node (ref "R155") (pin "2") (pinfunction "2_2") (pintype "passive"))
      (node (ref "R163") (pin "2") (pinfunction "2_2") (pintype "passive"))
      (node (ref "TP102") (pin "1") (pinfunction "G9_1") (pintype "passive"))
      (node (ref "VD26") (pin "2") (pinfunction "A_2") (pintype "passive"))
    )
    (net (code "22") (name "Net-(D24-C)") (class "Default")
      (node (ref "D24") (pin "1") (pinfunction "C_1") (pintype "passive"))
      (node (ref "R155") (pin "1") (pinfunction "1_1") (pintype "passive"))
      (node (ref "U38") (pin "15") (pinfunction "OUTA_15") (pintype "output"))
    )
    (net (code "23") (name "Net-(D25-A)") (class "Default")
      (node (ref "D25") (pin "2") (pinfunction "A_2") (pintype "passive"))
      (node (ref "J46") (pin "1") (pinfunction "0_1") (pintype "passive"))
      (node (ref "R162") (pin "2") (pinfunction "2_2") (pintype "passive"))
      (node (ref "R165") (pin "2") (pinfunction "2_2") (pintype "passive"))
      (node (ref "TP103") (pin "1") (pinfunction "G9_1") (pintype "passive"))
      (node (ref "VD27") (pin "2") (pinfunction "A_2") (pintype "passive"))
    )
    (net (code "24") (name "Net-(D25-C)") (class "Default")
      (node (ref "D25") (pin "1") (pinfunction "C_1") (pintype "passive"))
      (node (ref "R162") (pin "1") (pinfunction "1_1") (pintype "passive"))
      (node (ref "U39") (pin "15") (pinfunction "OUTA_15") (pintype "output"))
    )
    (net (code "25") (name "Net-(D26-A)") (class "Default")
      (node (ref "D26") (pin "2") (pinfunction "A_2") (pintype "passive"))
      (node (ref "J49") (pin "1") (pinfunction "0_1") (pintype "passive"))
      (node (ref "R171") (pin "2") (pinfunction "2_2") (pintype "passive"))
      (node (ref "R173") (pin "2") (pinfunction "2_2") (pintype "passive"))
      (node (ref "TP106") (pin "1") (pinfunction "G9_1") (pintype "passive"))
      (node (ref "VD30") (pin "2") (pinfunction "A_2") (pintype "passive"))
    )
    (net (code "26") (name "Net-(D26-C)") (class "Default")
      (node (ref "D26") (pin "1") (pinfunction "C_1") (pintype "passive"))
      (node (ref "R171") (pin "1") (pinfunction "1_1") (pintype "passive"))
      (node (ref "U38") (pin "10") (pinfunction "OUTB_10") (pintype "output"))
    )
    (net (code "27") (name "Net-(D27-A)") (class "Default")
      (node (ref "D27") (pin "2") (pinfunction "A_2") (pintype "passive"))
      (node (ref "J50") (pin "1") (pinfunction "0_1") (pintype "passive"))
      (node (ref "R172") (pin "2") (pinfunction "2_2") (pintype "passive"))
      (node (ref "R175") (pin "2") (pinfunction "2_2") (pintype "passive"))
      (node (ref "TP107") (pin "1") (pinfunction "G9_1") (pintype "passive"))
      (node (ref "VD31") (pin "2") (pinfunction "A_2") (pintype "passive"))
    )
    (net (code "28") (name "Net-(D27-C)") (class "Default")
      (node (ref "D27") (pin "1") (pinfunction "C_1") (pintype "passive"))
      (node (ref "R172") (pin "1") (pinfunction "1_1") (pintype "passive"))
      (node (ref "U39") (pin "10") (pinfunction "OUTB_10") (pintype "output"))
    )
    (net (code "29") (name "Net-(U38-DT)") (class "Default")
      (node (ref "C178") (pin "2") (pinfunction "2_2") (pintype "passive"))
      (node (ref "R167") (pin "2") (pinfunction "2_2") (pintype "passive"))
      (node (ref "U38") (pin "6") (pinfunction "DT_6") (pintype "input"))
    )
    (net (code "30") (name "Net-(U39-DT)") (class "Default")
      (node (ref "C184") (pin "2") (pinfunction "2_2") (pintype "passive"))
      (node (ref "R169") (pin "2") (pinfunction "2_2") (pintype "passive"))
      (node (ref "U39") (pin "6") (pinfunction "DT_6") (pintype "input"))
    )
    (net (code "31") (name "unconnected-(U38-NC-Pad7)") (class "Default")
      (node (ref "U38") (pin "7") (pinfunction "NC_7") (pintype "passive"))
    )
    (net (code "32") (name "unconnected-(U38-NC-Pad12)") (class "Default")
      (node (ref "U38") (pin "12") (pinfunction "NC_12") (pintype "passive"))
    )
    (net (code "33") (name "unconnected-(U38-NC-Pad13)") (class "Default")
      (node (ref "U38") (pin "13") (pinfunction "NC_13") (pintype "passive"))
    )
    (net (code "34") (name "unconnected-(U39-NC-Pad7)") (class "Default")
      (node (ref "U39") (pin "7") (pinfunction "NC_7") (pintype "passive"))
    )
    (net (code "35") (name "unconnected-(U39-NC-Pad12)") (class "Default")
      (node (ref "U39") (pin "12") (pinfunction "NC_12") (pintype "passive"))
    )
    (net (code "36") (name "unconnected-(U39-NC-Pad13)") (class "Default")
      (node (ref "U39") (pin "13") (pinfunction "NC_13") (pintype "passive"))
    )
  )
)
